# esp8266_relay_board.net
KiCad netlist of a schematic drawn in EAGLE
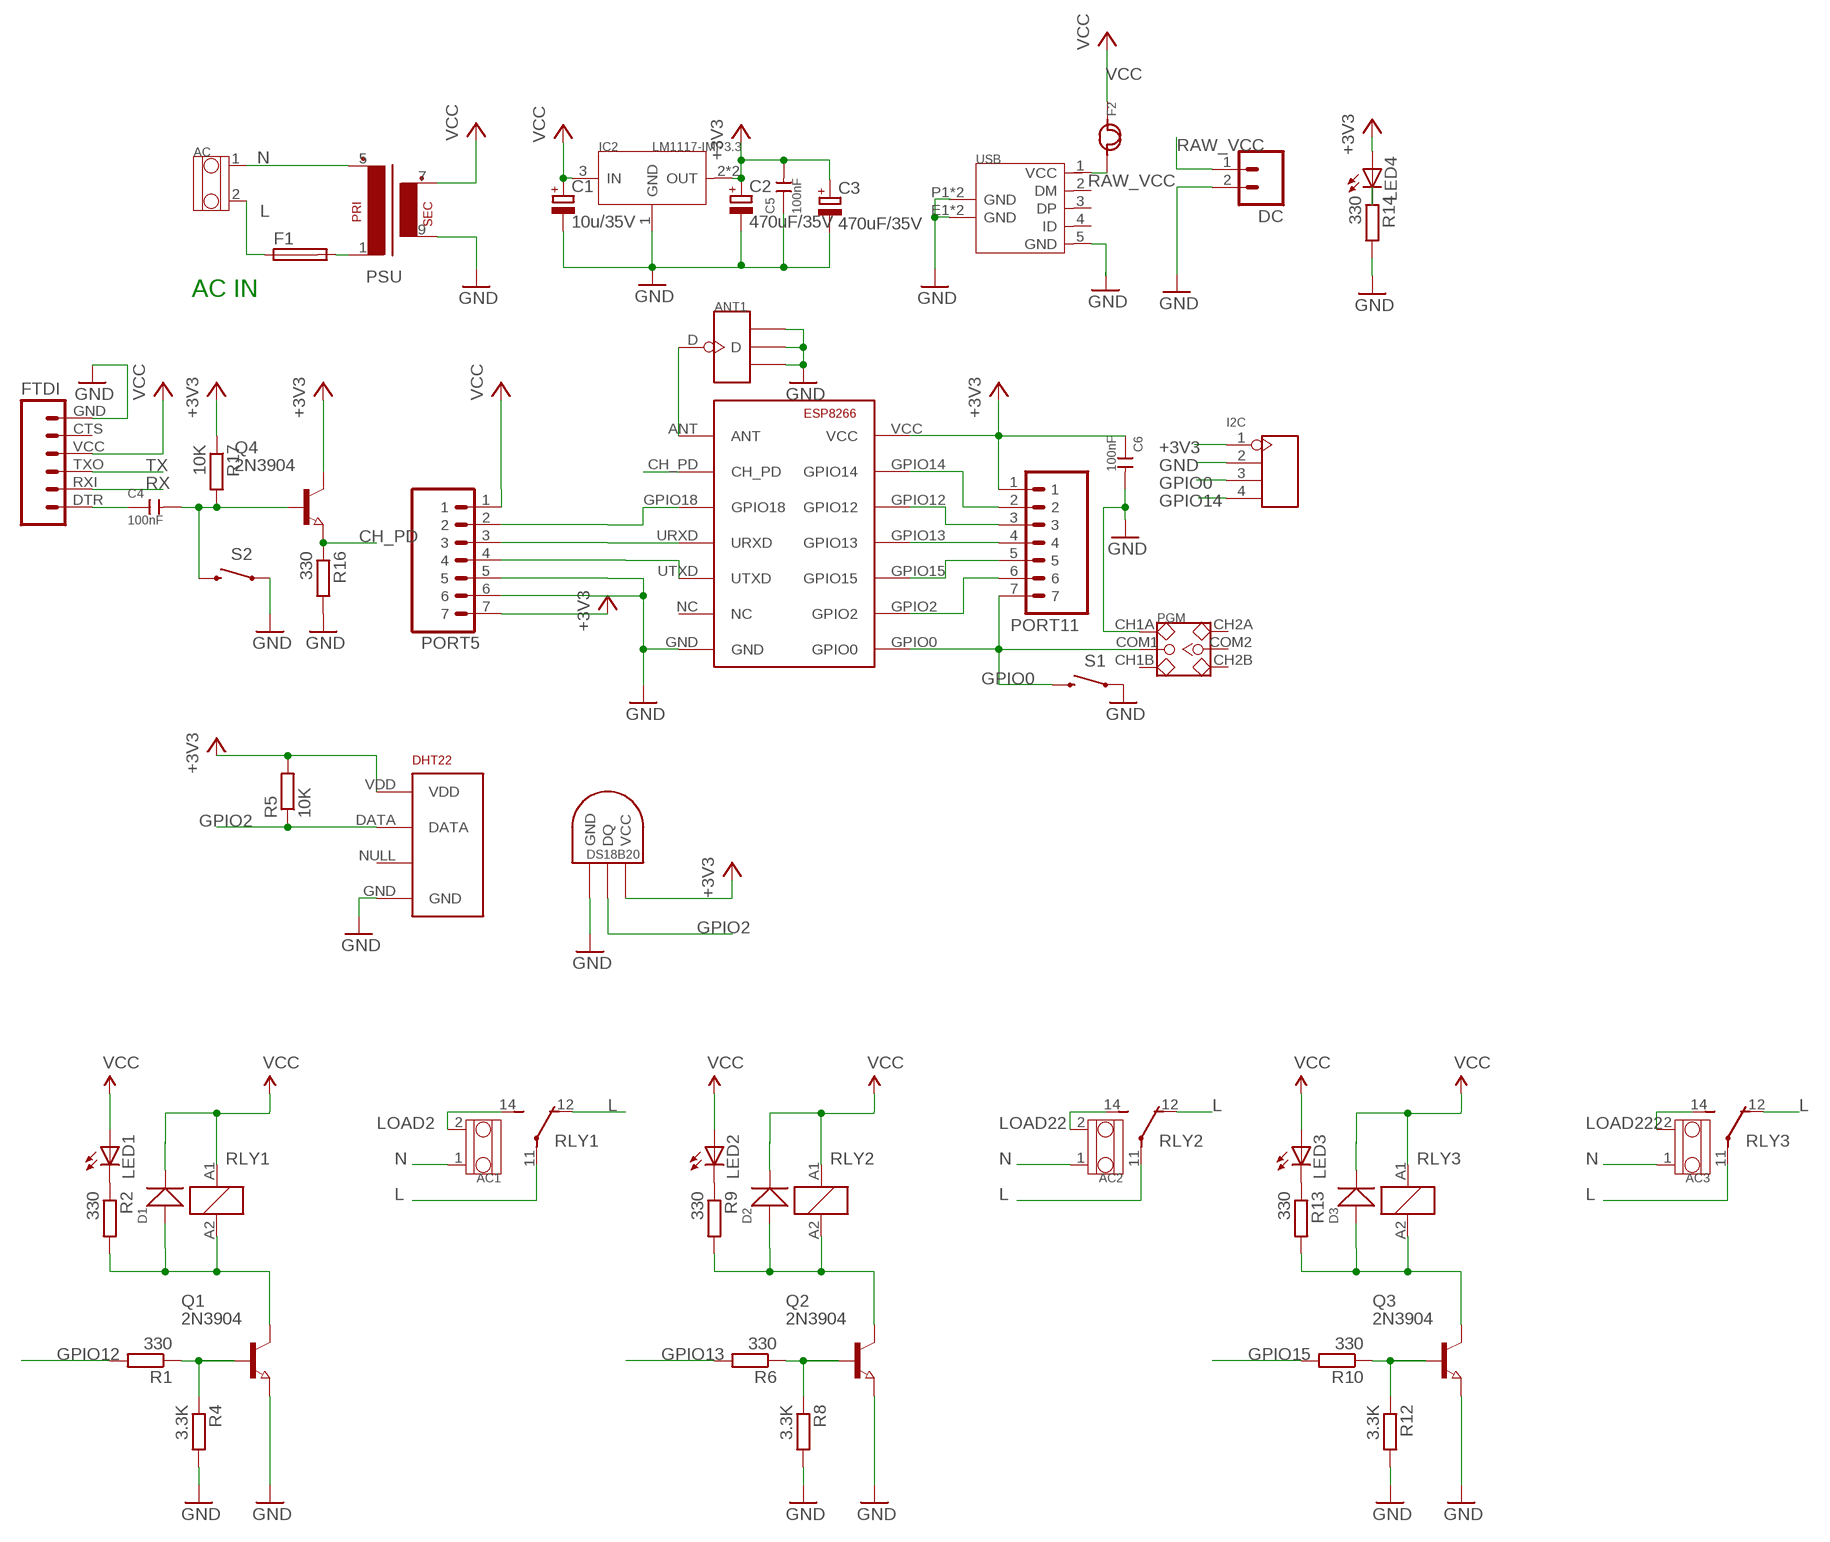
[diagram p0: schematic, sheet 1]

(export (version "E")
  (design (tool "Eeschema 10.0.6"))
  (components
    (comp (ref "AC")
      (value "SCREW-TERMINAL-2P-3470110P1")
      (footprint "eagle-import:2P-5.0")
      (libsource (lib "eagle-import") (part "SCREW-TERMINAL-2P-3470110P1"))
    )
    (comp (ref "AC1")
      (value "SCREW-TERMINAL-2P-3470110P1")
      (footprint "eagle-import:2P-5.0")
      (libsource (lib "eagle-import") (part "SCREW-TERMINAL-2P-3470110P1"))
    )
    (comp (ref "AC2")
      (value "SCREW-TERMINAL-2P-3470110P1")
      (footprint "eagle-import:2P-5.0")
      (libsource (lib "eagle-import") (part "SCREW-TERMINAL-2P-3470110P1"))
    )
    (comp (ref "AC3")
      (value "SCREW-TERMINAL-2P-3470110P1")
      (footprint "eagle-import:2P-5.0")
      (libsource (lib "eagle-import") (part "SCREW-TERMINAL-2P-3470110P1"))
    )
    (comp (ref "ANT1")
      (value "U-FL-CONNECTOR-3450020P1")
      (footprint "eagle-import:U-FL")
      (libsource (lib "eagle-import") (part "U-FL-CONNECTOR-3450020P1"))
    )
    (comp (ref "C1")
      (value "10u/35V")
      (footprint "eagle-import:SMC_C")
      (libsource (lib "eagle-import") (part "CPOL-EUSMCC"))
    )
    (comp (ref "C2")
      (value "470uF/35V")
      (footprint "eagle-import:SMC_C")
      (libsource (lib "eagle-import") (part "CPOL-EUSMCC"))
    )
    (comp (ref "C3")
      (value "470uF/35V")
      (footprint "eagle-import:SMC_C")
      (libsource (lib "eagle-import") (part "CPOL-EUSMCC"))
    )
    (comp (ref "C4")
      (value "100nF")
      (footprint "eagle-import:C0603")
      (libsource (lib "eagle-import") (part "CAP-0603"))
    )
    (comp (ref "C5")
      (value "100nF")
      (footprint "eagle-import:C0603")
      (libsource (lib "eagle-import") (part "CAP-0603"))
    )
    (comp (ref "C6")
      (value "100nF")
      (footprint "eagle-import:C0603")
      (libsource (lib "eagle-import") (part "CAP-0603"))
    )
    (comp (ref "D1")
      (value "DIODE'1206'")
      (footprint "eagle-import:SOD-123")
      (libsource (lib "eagle-import") (part "DIODE'1206'"))
    )
    (comp (ref "D2")
      (value "DIODE'1206'")
      (footprint "eagle-import:SOD-123")
      (libsource (lib "eagle-import") (part "DIODE'1206'"))
    )
    (comp (ref "D3")
      (value "DIODE'1206'")
      (footprint "eagle-import:SOD-123")
      (libsource (lib "eagle-import") (part "DIODE'1206'"))
    )
    (comp (ref "DC")
      (value "M02LOCK")
      (footprint "eagle-import:1X02_LOCK")
      (libsource (lib "eagle-import") (part "M02LOCK"))
    )
    (comp (ref "DHT22")
      (value "RHT03_DHT-22_AM2302")
      (footprint "eagle-import:RHT03_DHT-22")
      (libsource (lib "eagle-import") (part "RHT03_DHT-22_AM2302"))
    )
    (comp (ref "ESP8266")
      (value "ESP8266")
      (footprint "eagle-import:ESP-04")
      (libsource (lib "eagle-import") (part "ESP8266-04"))
    )
    (comp (ref "F1")
      (value "FUSEBLANK_5X20MM")
      (footprint "eagle-import:FUSE_HOLDER_5X20MM")
      (libsource (lib "eagle-import") (part "FUSEBLANK_5X20MM"))
    )
    (comp (ref "F2")
      (value "FUSE-1206")
      (footprint "eagle-import:F1206")
      (libsource (lib "eagle-import") (part "FUSE-1206"))
    )
    (comp (ref "FTDI")
      (value "FTDI_BASICPTH")
      (footprint "eagle-import:FTDI_BASIC")
      (libsource (lib "eagle-import") (part "FTDI_BASICPTH"))
    )
    (comp (ref "I2C")
      (value "HEADER-4P-65/35MIL")
      (footprint "eagle-import:4P-2.54-65_35MIL")
      (libsource (lib "eagle-import") (part "HEADER-4P-65/35MIL"))
    )
    (comp (ref "IC2")
      (value "LM1117-IMP3.3")
      (footprint "eagle-import:SOT223")
      (libsource (lib "eagle-import") (part "CJ1117-3.3-1310190P1"))
    )
    (comp (ref "LED1")
      (value "LEDSML0603")
      (footprint "eagle-import:SML0603")
      (libsource (lib "eagle-import") (part "LEDSML0603"))
    )
    (comp (ref "LED2")
      (value "LEDSML0603")
      (footprint "eagle-import:SML0603")
      (libsource (lib "eagle-import") (part "LEDSML0603"))
    )
    (comp (ref "LED3")
      (value "LEDSML0603")
      (footprint "eagle-import:SML0603")
      (libsource (lib "eagle-import") (part "LEDSML0603"))
    )
    (comp (ref "LED4")
      (value "LEDSML0603")
      (footprint "eagle-import:SML0603")
      (libsource (lib "eagle-import") (part "LEDSML0603"))
    )
    (comp (ref "PGM")
      (value "SWITCH-2CH-6P-90D")
      (footprint "eagle-import:6P-2CH-2.54-L9.0XW3.5XH3.2-90D")
      (libsource (lib "eagle-import") (part "SWITCH-2CH-6P-90D"))
    )
    (comp (ref "PORT5")
      (value "CON7PIN-PAD")
      (footprint "eagle-import:PORT7PAD")
      (libsource (lib "eagle-import") (part "CON7PIN-PAD"))
    )
    (comp (ref "PORT11")
      (value "CON7PIN-PAD")
      (footprint "eagle-import:PORT7PAD")
      (libsource (lib "eagle-import") (part "CON7PIN-PAD"))
    )
    (comp (ref "PSU")
      (value "VV11")
      (footprint "eagle-import:VV11")
      (libsource (lib "eagle-import") (part "VV11"))
    )
    (comp (ref "Q1")
      (value "2N3904")
      (footprint "eagle-import:SOT23")
      (libsource (lib "eagle-import") (part "NPN-TRANSISTOR_SOT23"))
    )
    (comp (ref "Q2")
      (value "2N3904")
      (footprint "eagle-import:SOT23")
      (libsource (lib "eagle-import") (part "NPN-TRANSISTOR_SOT23"))
    )
    (comp (ref "Q3")
      (value "2N3904")
      (footprint "eagle-import:SOT23")
      (libsource (lib "eagle-import") (part "NPN-TRANSISTOR_SOT23"))
    )
    (comp (ref "Q4")
      (value "2N3904")
      (footprint "eagle-import:SOT23")
      (libsource (lib "eagle-import") (part "NPN-TRANSISTOR_SOT23"))
    )
    (comp (ref "R1")
      (value "330")
      (footprint "eagle-import:R0603")
      (libsource (lib "eagle-import") (part "R-EU_R0603"))
    )
    (comp (ref "R2")
      (value "330")
      (footprint "eagle-import:R0603")
      (libsource (lib "eagle-import") (part "R-EU_R0603"))
    )
    (comp (ref "R4")
      (value "3.3K")
      (footprint "eagle-import:R0603")
      (libsource (lib "eagle-import") (part "R-EU_R0603"))
    )
    (comp (ref "R5")
      (value "10K")
      (footprint "eagle-import:R0603")
      (libsource (lib "eagle-import") (part "R-EU_R0603"))
    )
    (comp (ref "R6")
      (value "330")
      (footprint "eagle-import:R0603")
      (libsource (lib "eagle-import") (part "R-EU_R0603"))
    )
    (comp (ref "R8")
      (value "3.3K")
      (footprint "eagle-import:R0603")
      (libsource (lib "eagle-import") (part "R-EU_R0603"))
    )
    (comp (ref "R9")
      (value "330")
      (footprint "eagle-import:R0603")
      (libsource (lib "eagle-import") (part "R-EU_R0603"))
    )
    (comp (ref "R10")
      (value "330")
      (footprint "eagle-import:R0603")
      (libsource (lib "eagle-import") (part "R-EU_R0603"))
    )
    (comp (ref "R12")
      (value "3.3K")
      (footprint "eagle-import:R0603")
      (libsource (lib "eagle-import") (part "R-EU_R0603"))
    )
    (comp (ref "R13")
      (value "330")
      (footprint "eagle-import:R0603")
      (libsource (lib "eagle-import") (part "R-EU_R0603"))
    )
    (comp (ref "R14")
      (value "330")
      (footprint "eagle-import:R0603")
      (libsource (lib "eagle-import") (part "R-EU_R0603"))
    )
    (comp (ref "R16")
      (value "330")
      (footprint "eagle-import:R0603")
      (libsource (lib "eagle-import") (part "R-EU_R0603"))
    )
    (comp (ref "R17")
      (value "10K")
      (footprint "eagle-import:R0603")
      (libsource (lib "eagle-import") (part "R-EU_R0603"))
    )
    (comp (ref "RLY1")
      (value "RT114005")
      (footprint "eagle-import:RT-C_O12A3.5")
      (libsource (lib "eagle-import") (part "RT?114005"))
    )
    (comp (ref "RLY2")
      (value "RT114005")
      (footprint "eagle-import:RT-C_O12A3.5")
      (libsource (lib "eagle-import") (part "RT?114005"))
    )
    (comp (ref "RLY3")
      (value "RT114005")
      (footprint "eagle-import:RT-C_O12A3.5")
      (libsource (lib "eagle-import") (part "RT?114005"))
    )
    (comp (ref "S1")
      (value "!RESET")
      (footprint "eagle-import:TACTILE_SWITCH_SMD")
      (libsource (lib "eagle-import") (part "SWITCH-MOMENTARY-2SMD"))
    )
    (comp (ref "S2")
      (value "!RESET")
      (footprint "eagle-import:TACTILE_SWITCH_SMD")
      (libsource (lib "eagle-import") (part "SWITCH-MOMENTARY-2SMD"))
    )
    (comp (ref "U$1")
      (value "DS1820TO92")
      (footprint "eagle-import:DS1820")
      (libsource (lib "eagle-import") (part "DS1820TO92"))
    )
    (comp (ref "USB")
      (value "MICRO-USB-5P-340015001")
      (footprint "eagle-import:B-SMD-5P")
      (libsource (lib "eagle-import") (part "MICRO-USB-5P-340015001"))
    )
  )
  (nets
    (net (code "1") (name "+3V3") (class "Default")
      (node (ref "C2") (pin "+") (pinfunction "+_+") (pintype "passive"))
      (node (ref "C3") (pin "+") (pinfunction "+_+") (pintype "passive"))
      (node (ref "C5") (pin "2") (pinfunction "2_2") (pintype "passive"))
      (node (ref "C6") (pin "1") (pinfunction "1_1") (pintype "passive"))
      (node (ref "DHT22") (pin "VDD") (pinfunction "VDD_VDD") (pintype "power_in"))
      (node (ref "ESP8266") (pin "VCC") (pinfunction "VCC_VCC") (pintype "bidirectional"))
      (node (ref "I2C") (pin "1") (pinfunction "P$1_1") (pintype "bidirectional"))
      (node (ref "IC2") (pin "2") (pinfunction "OUT_2") (pintype "bidirectional"))
      (node (ref "IC2") (pin "TER") (pinfunction "OUT_TER") (pintype "bidirectional"))
      (node (ref "LED4") (pin "A") (pinfunction "A_A") (pintype "passive"))
      (node (ref "PORT11") (pin "1") (pinfunction "1_1") (pintype "bidirectional"))
      (node (ref "PORT5") (pin "7") (pinfunction "7_7") (pintype "bidirectional"))
      (node (ref "Q4") (pin "3") (pinfunction "C_3") (pintype "passive"))
      (node (ref "R17") (pin "1") (pinfunction "1_1") (pintype "passive"))
      (node (ref "R5") (pin "2") (pinfunction "2_2") (pintype "passive"))
      (node (ref "U$1") (pin "VDD") (pinfunction "VCC_VDD") (pintype "power_in"))
    )
    (net (code "2") (name "/CH_PD") (class "Default")
      (node (ref "ESP8266") (pin "CH_PD") (pinfunction "CH_PD_CH_PD") (pintype "bidirectional"))
      (node (ref "Q4") (pin "2") (pinfunction "E_2") (pintype "passive"))
      (node (ref "R16") (pin "1") (pinfunction "1_1") (pintype "passive"))
    )
    (net (code "3") (name "/GPIO0") (class "Default")
      (node (ref "ESP8266") (pin "GPIO0") (pinfunction "GPIO0_GPIO0") (pintype "bidirectional"))
      (node (ref "I2C") (pin "3") (pinfunction "P$3_3") (pintype "bidirectional"))
      (node (ref "PGM") (pin "COM1") (pinfunction "COM1_COM1") (pintype "bidirectional"))
      (node (ref "PORT11") (pin "7") (pinfunction "7_7") (pintype "bidirectional"))
      (node (ref "S1") (pin "3") (pinfunction "2_3") (pintype "passive"))
    )
    (net (code "4") (name "/GPIO2") (class "Default")
      (node (ref "DHT22") (pin "DATA") (pinfunction "DATA_DATA") (pintype "bidirectional"))
      (node (ref "ESP8266") (pin "GPIO2") (pinfunction "GPIO2_GPIO2") (pintype "bidirectional"))
      (node (ref "PORT11") (pin "6") (pinfunction "6_6") (pintype "bidirectional"))
      (node (ref "R5") (pin "1") (pinfunction "1_1") (pintype "passive"))
      (node (ref "U$1") (pin "DQ") (pinfunction "DQ_DQ") (pintype "bidirectional"))
    )
    (net (code "5") (name "/GPIO12") (class "Default")
      (node (ref "ESP8266") (pin "GPIO12") (pinfunction "GPIO12_GPIO12") (pintype "bidirectional"))
      (node (ref "PORT11") (pin "3") (pinfunction "3_3") (pintype "bidirectional"))
      (node (ref "R1") (pin "2") (pinfunction "2_2") (pintype "passive"))
    )
    (net (code "6") (name "/GPIO13") (class "Default")
      (node (ref "ESP8266") (pin "GPIO13") (pinfunction "GPIO13_GPIO13") (pintype "bidirectional"))
      (node (ref "PORT11") (pin "4") (pinfunction "4_4") (pintype "bidirectional"))
      (node (ref "R6") (pin "2") (pinfunction "2_2") (pintype "passive"))
    )
    (net (code "7") (name "/GPIO14") (class "Default")
      (node (ref "ESP8266") (pin "GPIO14") (pinfunction "GPIO14_GPIO14") (pintype "bidirectional"))
      (node (ref "I2C") (pin "4") (pinfunction "P$4_4") (pintype "bidirectional"))
      (node (ref "PORT11") (pin "2") (pinfunction "2_2") (pintype "bidirectional"))
    )
    (net (code "8") (name "/GPIO15") (class "Default")
      (node (ref "ESP8266") (pin "GPIO15") (pinfunction "GPIO15_GPIO15") (pintype "bidirectional"))
      (node (ref "PORT11") (pin "5") (pinfunction "5_5") (pintype "bidirectional"))
      (node (ref "R10") (pin "2") (pinfunction "2_2") (pintype "passive"))
    )
    (net (code "9") (name "/L") (class "Default")
      (node (ref "AC") (pin "2") (pinfunction "2_2") (pintype "bidirectional"))
      (node (ref "F1") (pin "1") (pinfunction "1_1") (pintype "passive"))
      (node (ref "RLY1") (pin "11") (pinfunction "P_11") (pintype "passive"))
      (node (ref "RLY1") (pin "12") (pinfunction "O_12") (pintype "passive"))
      (node (ref "RLY2") (pin "11") (pinfunction "P_11") (pintype "passive"))
      (node (ref "RLY2") (pin "12") (pinfunction "O_12") (pintype "passive"))
      (node (ref "RLY3") (pin "11") (pinfunction "P_11") (pintype "passive"))
      (node (ref "RLY3") (pin "12") (pinfunction "O_12") (pintype "passive"))
    )
    (net (code "10") (name "/LOAD2") (class "Default")
      (node (ref "AC1") (pin "2") (pinfunction "2_2") (pintype "bidirectional"))
      (node (ref "RLY1") (pin "14") (pinfunction "S_14") (pintype "passive"))
    )
    (net (code "11") (name "/LOAD22") (class "Default")
      (node (ref "AC2") (pin "2") (pinfunction "2_2") (pintype "bidirectional"))
      (node (ref "RLY2") (pin "14") (pinfunction "S_14") (pintype "passive"))
    )
    (net (code "12") (name "/LOAD222") (class "Default")
      (node (ref "AC3") (pin "2") (pinfunction "2_2") (pintype "bidirectional"))
      (node (ref "RLY3") (pin "14") (pinfunction "S_14") (pintype "passive"))
    )
    (net (code "13") (name "/N") (class "Default")
      (node (ref "AC") (pin "1") (pinfunction "1_1") (pintype "bidirectional"))
      (node (ref "AC1") (pin "1") (pinfunction "1_1") (pintype "bidirectional"))
      (node (ref "AC2") (pin "1") (pinfunction "1_1") (pintype "bidirectional"))
      (node (ref "AC3") (pin "1") (pinfunction "1_1") (pintype "bidirectional"))
      (node (ref "PSU") (pin "5") (pinfunction "P2_5") (pintype "passive"))
    )
    (net (code "14") (name "/RAW_VCC") (class "Default")
      (node (ref "DC") (pin "1") (pinfunction "1_1") (pintype "passive"))
      (node (ref "F2") (pin "2") (pinfunction "2_2") (pintype "bidirectional"))
      (node (ref "USB") (pin "1") (pinfunction "VCC_1") (pintype "bidirectional"))
    )
    (net (code "15") (name "/RX") (class "Default")
      (node (ref "ESP8266") (pin "UTXD") (pinfunction "UTXD_UTXD") (pintype "bidirectional"))
      (node (ref "FTDI") (pin "RXI") (pinfunction "2_RXI") (pintype "passive"))
      (node (ref "PORT5") (pin "4") (pinfunction "4_4") (pintype "bidirectional"))
    )
    (net (code "16") (name "/TX") (class "Default")
      (node (ref "ESP8266") (pin "URXD") (pinfunction "URXD_URXD") (pintype "bidirectional"))
      (node (ref "FTDI") (pin "TXO") (pinfunction "3_TXO") (pintype "passive"))
      (node (ref "PORT5") (pin "3") (pinfunction "3_3") (pintype "bidirectional"))
    )
    (net (code "17") (name "GND") (class "Default")
      (node (ref "ANT1") (pin "GND1") (pinfunction "GND1_GND1") (pintype "bidirectional"))
      (node (ref "ANT1") (pin "GND2") (pinfunction "GND2_GND2") (pintype "bidirectional"))
      (node (ref "ANT1") (pin "GND3") (pinfunction "GND3_GND3") (pintype "bidirectional"))
      (node (ref "C1") (pin "-") (pinfunction "-_-") (pintype "passive"))
      (node (ref "C2") (pin "-") (pinfunction "-_-") (pintype "passive"))
      (node (ref "C3") (pin "-") (pinfunction "-_-") (pintype "passive"))
      (node (ref "C5") (pin "1") (pinfunction "1_1") (pintype "passive"))
      (node (ref "C6") (pin "2") (pinfunction "2_2") (pintype "passive"))
      (node (ref "DC") (pin "2") (pinfunction "2_2") (pintype "passive"))
      (node (ref "DHT22") (pin "GND") (pinfunction "GND_GND") (pintype "power_in"))
      (node (ref "ESP8266") (pin "GND") (pinfunction "GND_GND") (pintype "bidirectional"))
      (node (ref "FTDI") (pin "GND") (pinfunction "6_GND") (pintype "passive"))
      (node (ref "I2C") (pin "2") (pinfunction "P$2_2") (pintype "bidirectional"))
      (node (ref "IC2") (pin "1") (pinfunction "GND_1") (pintype "bidirectional"))
      (node (ref "PGM") (pin "CH1A") (pinfunction "CH1A_CH1A") (pintype "bidirectional"))
      (node (ref "PORT5") (pin "5") (pinfunction "5_5") (pintype "bidirectional"))
      (node (ref "PORT5") (pin "6") (pinfunction "6_6") (pintype "bidirectional"))
      (node (ref "PSU") (pin "9") (pinfunction "S4_9") (pintype "passive"))
      (node (ref "Q1") (pin "2") (pinfunction "E_2") (pintype "passive"))
      (node (ref "Q2") (pin "2") (pinfunction "E_2") (pintype "passive"))
      (node (ref "Q3") (pin "2") (pinfunction "E_2") (pintype "passive"))
      (node (ref "R12") (pin "2") (pinfunction "2_2") (pintype "passive"))
      (node (ref "R14") (pin "2") (pinfunction "2_2") (pintype "passive"))
      (node (ref "R16") (pin "2") (pinfunction "2_2") (pintype "passive"))
      (node (ref "R4") (pin "2") (pinfunction "2_2") (pintype "passive"))
      (node (ref "R8") (pin "2") (pinfunction "2_2") (pintype "passive"))
      (node (ref "S1") (pin "1") (pinfunction "1_1") (pintype "passive"))
      (node (ref "S2") (pin "1") (pinfunction "1_1") (pintype "passive"))
      (node (ref "U$1") (pin "GND") (pinfunction "GND_GND") (pintype "power_in"))
      (node (ref "USB") (pin "5") (pinfunction "GND_5") (pintype "bidirectional"))
      (node (ref "USB") (pin "E1") (pinfunction "GND_E1") (pintype "bidirectional"))
      (node (ref "USB") (pin "E2") (pinfunction "GND_E2") (pintype "bidirectional"))
      (node (ref "USB") (pin "P1") (pinfunction "GND_P1") (pintype "bidirectional"))
      (node (ref "USB") (pin "P2") (pinfunction "GND_P2") (pintype "bidirectional"))
    )
    (net (code "18") (name "Net-(ANT1-PadD)") (class "Default")
      (node (ref "ANT1") (pin "D") (pinfunction "D_D") (pintype "bidirectional"))
      (node (ref "ESP8266") (pin "ANT") (pinfunction "ANT_ANT") (pintype "bidirectional"))
    )
    (net (code "19") (name "Net-(ESP8266-PadGPIO18)") (class "Default")
      (node (ref "ESP8266") (pin "GPIO18") (pinfunction "GPIO18_GPIO18") (pintype "bidirectional"))
      (node (ref "PORT5") (pin "2") (pinfunction "2_2") (pintype "bidirectional"))
    )
    (net (code "20") (name "Net-(FTDI-1)") (class "Default")
      (node (ref "C4") (pin "1") (pinfunction "1_1") (pintype "passive"))
      (node (ref "FTDI") (pin "DTR") (pinfunction "1_DTR") (pintype "passive"))
    )
    (net (code "21") (name "Net-(LED1-PadC)") (class "Default")
      (node (ref "LED1") (pin "C") (pinfunction "C_C") (pintype "passive"))
      (node (ref "R2") (pin "1") (pinfunction "1_1") (pintype "passive"))
    )
    (net (code "22") (name "Net-(LED2-PadC)") (class "Default")
      (node (ref "LED2") (pin "C") (pinfunction "C_C") (pintype "passive"))
      (node (ref "R9") (pin "1") (pinfunction "1_1") (pintype "passive"))
    )
    (net (code "23") (name "Net-(LED3-PadC)") (class "Default")
      (node (ref "LED3") (pin "C") (pinfunction "C_C") (pintype "passive"))
      (node (ref "R13") (pin "1") (pinfunction "1_1") (pintype "passive"))
    )
    (net (code "24") (name "Net-(LED4-PadC)") (class "Default")
      (node (ref "LED4") (pin "C") (pinfunction "C_C") (pintype "passive"))
      (node (ref "R14") (pin "1") (pinfunction "1_1") (pintype "passive"))
    )
    (net (code "25") (name "Net-(PSU-P1)") (class "Default")
      (node (ref "F1") (pin "2") (pinfunction "2_2") (pintype "passive"))
      (node (ref "PSU") (pin "1") (pinfunction "P1_1") (pintype "passive"))
    )
    (net (code "26") (name "Net-(Q1-B)") (class "Default")
      (node (ref "Q1") (pin "1") (pinfunction "B_1") (pintype "passive"))
      (node (ref "R1") (pin "1") (pinfunction "1_1") (pintype "passive"))
      (node (ref "R4") (pin "1") (pinfunction "1_1") (pintype "passive"))
    )
    (net (code "27") (name "Net-(Q1-C)") (class "Default")
      (node (ref "D1") (pin "+") (pinfunction "+_+") (pintype "passive"))
      (node (ref "Q1") (pin "3") (pinfunction "C_3") (pintype "passive"))
      (node (ref "R2") (pin "2") (pinfunction "2_2") (pintype "passive"))
      (node (ref "RLY1") (pin "A2") (pinfunction "2_A2") (pintype "passive"))
    )
    (net (code "28") (name "Net-(Q2-B)") (class "Default")
      (node (ref "Q2") (pin "1") (pinfunction "B_1") (pintype "passive"))
      (node (ref "R6") (pin "1") (pinfunction "1_1") (pintype "passive"))
      (node (ref "R8") (pin "1") (pinfunction "1_1") (pintype "passive"))
    )
    (net (code "29") (name "Net-(Q2-C)") (class "Default")
      (node (ref "D2") (pin "+") (pinfunction "+_+") (pintype "passive"))
      (node (ref "Q2") (pin "3") (pinfunction "C_3") (pintype "passive"))
      (node (ref "R9") (pin "2") (pinfunction "2_2") (pintype "passive"))
      (node (ref "RLY2") (pin "A2") (pinfunction "2_A2") (pintype "passive"))
    )
    (net (code "30") (name "Net-(Q3-B)") (class "Default")
      (node (ref "Q3") (pin "1") (pinfunction "B_1") (pintype "passive"))
      (node (ref "R10") (pin "1") (pinfunction "1_1") (pintype "passive"))
      (node (ref "R12") (pin "1") (pinfunction "1_1") (pintype "passive"))
    )
    (net (code "31") (name "Net-(Q3-C)") (class "Default")
      (node (ref "D3") (pin "+") (pinfunction "+_+") (pintype "passive"))
      (node (ref "Q3") (pin "3") (pinfunction "C_3") (pintype "passive"))
      (node (ref "R13") (pin "2") (pinfunction "2_2") (pintype "passive"))
      (node (ref "RLY3") (pin "A2") (pinfunction "2_A2") (pintype "passive"))
    )
    (net (code "32") (name "Net-(Q4-B)") (class "Default")
      (node (ref "C4") (pin "2") (pinfunction "2_2") (pintype "passive"))
      (node (ref "Q4") (pin "1") (pinfunction "B_1") (pintype "passive"))
      (node (ref "R17") (pin "2") (pinfunction "2_2") (pintype "passive"))
      (node (ref "S2") (pin "3") (pinfunction "2_3") (pintype "passive"))
    )
    (net (code "33") (name "VCC") (class "Default")
      (node (ref "C1") (pin "+") (pinfunction "+_+") (pintype "passive"))
      (node (ref "D1") (pin "-") (pinfunction "-_-") (pintype "passive"))
      (node (ref "D2") (pin "-") (pinfunction "-_-") (pintype "passive"))
      (node (ref "D3") (pin "-") (pinfunction "-_-") (pintype "passive"))
      (node (ref "F2") (pin "1") (pinfunction "1_1") (pintype "bidirectional"))
      (node (ref "FTDI") (pin "VCC") (pinfunction "4_VCC") (pintype "passive"))
      (node (ref "IC2") (pin "3") (pinfunction "IN_3") (pintype "bidirectional"))
      (node (ref "LED1") (pin "A") (pinfunction "A_A") (pintype "passive"))
      (node (ref "LED2") (pin "A") (pinfunction "A_A") (pintype "passive"))
      (node (ref "LED3") (pin "A") (pinfunction "A_A") (pintype "passive"))
      (node (ref "PORT5") (pin "1") (pinfunction "1_1") (pintype "bidirectional"))
      (node (ref "PSU") (pin "7") (pinfunction "S3_7") (pintype "passive"))
      (node (ref "RLY1") (pin "A1") (pinfunction "1_A1") (pintype "passive"))
      (node (ref "RLY2") (pin "A1") (pinfunction "1_A1") (pintype "passive"))
      (node (ref "RLY3") (pin "A1") (pinfunction "1_A1") (pintype "passive"))
    )
    (net (code "34") (name "unconnected-(DHT22-PadNULL)") (class "Default")
      (node (ref "DHT22") (pin "NULL") (pinfunction "NULL_NULL") (pintype "no_connect"))
    )
    (net (code "35") (name "unconnected-(ESP8266-PadNC)") (class "Default")
      (node (ref "ESP8266") (pin "NC") (pinfunction "NC_NC") (pintype "bidirectional"))
    )
    (net (code "36") (name "unconnected-(FTDI-5-PadCTS)") (class "Default")
      (node (ref "FTDI") (pin "CTS") (pinfunction "5_CTS") (pintype "passive"))
    )
    (net (code "37") (name "unconnected-(PGM-PadCH1B)") (class "Default")
      (node (ref "PGM") (pin "CH1B") (pinfunction "CH1B_CH1B") (pintype "bidirectional"))
    )
    (net (code "38") (name "unconnected-(PGM-PadCH2A)") (class "Default")
      (node (ref "PGM") (pin "CH2A") (pinfunction "CH2A_CH2A") (pintype "bidirectional"))
    )
    (net (code "39") (name "unconnected-(PGM-PadCH2B)") (class "Default")
      (node (ref "PGM") (pin "CH2B") (pinfunction "CH2B_CH2B") (pintype "bidirectional"))
    )
    (net (code "40") (name "unconnected-(PGM-PadCOM2)") (class "Default")
      (node (ref "PGM") (pin "COM2") (pinfunction "COM2_COM2") (pintype "bidirectional"))
    )
    (net (code "41") (name "unconnected-(USB-DM-Pad2)") (class "Default")
      (node (ref "USB") (pin "2") (pinfunction "DM_2") (pintype "bidirectional"))
    )
    (net (code "42") (name "unconnected-(USB-DP-Pad3)") (class "Default")
      (node (ref "USB") (pin "3") (pinfunction "DP_3") (pintype "bidirectional"))
    )
    (net (code "43") (name "unconnected-(USB-ID-Pad4)") (class "Default")
      (node (ref "USB") (pin "4") (pinfunction "ID_4") (pintype "bidirectional"))
    )
  )
)
